# shield_biasa.net
KiCad netlist of a schematic drawn in EAGLE
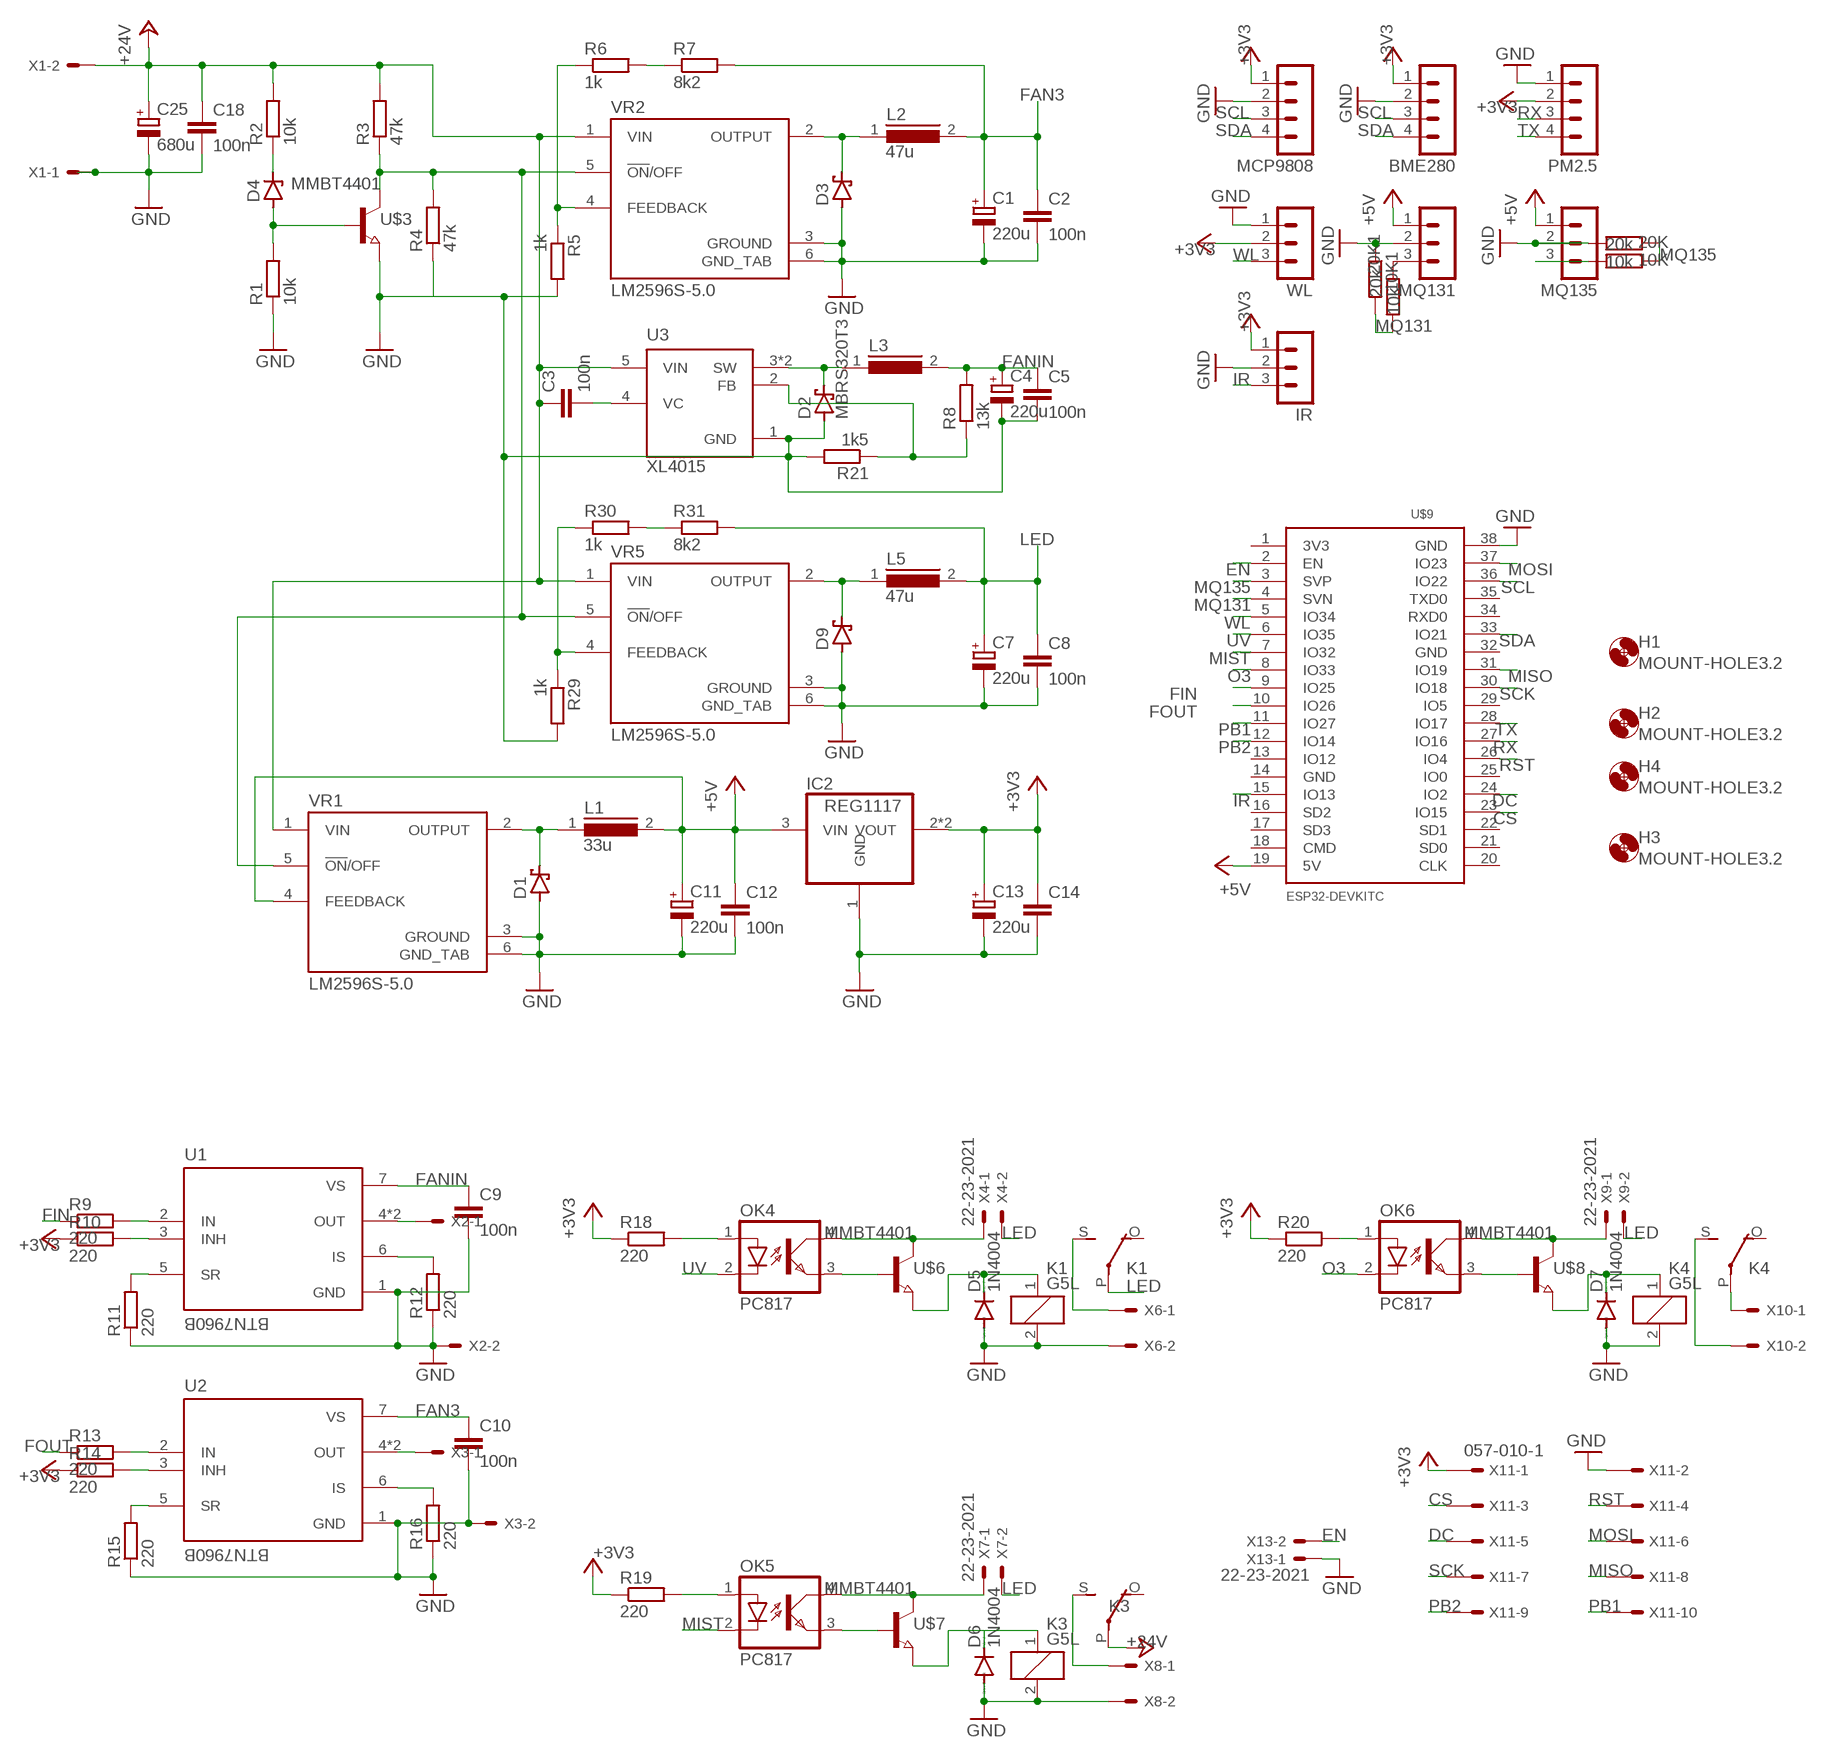
[diagram p0: schematic, sheet 1]

(export (version "E")
  (design (tool "Eeschema 10.0.6"))
  (components
    (comp (ref "10K")
      (value "10k")
      (footprint "eagle-import:R0805")
      (libsource (lib "eagle-import") (part "R-EU_R0805"))
    )
    (comp (ref "10K1")
      (value "10k")
      (footprint "eagle-import:R0805")
      (libsource (lib "eagle-import") (part "R-EU_R0805"))
    )
    (comp (ref "20K")
      (value "20k")
      (footprint "eagle-import:R0805")
      (libsource (lib "eagle-import") (part "R-EU_R0805"))
    )
    (comp (ref "20K1")
      (value "20k")
      (footprint "eagle-import:R0805")
      (libsource (lib "eagle-import") (part "R-EU_R0805"))
    )
    (comp (ref "BME280")
      (value "MA04-1")
      (footprint "eagle-import:MA04-1")
      (libsource (lib "eagle-import") (part "MA04-1"))
    )
    (comp (ref "C1")
      (value "220u")
      (footprint "eagle-import:153CLV-0605")
      (libsource (lib "eagle-import") (part "CPOL-EU153CLV-0605"))
    )
    (comp (ref "C2")
      (value "100n")
      (footprint "eagle-import:C0805")
      (libsource (lib "eagle-import") (part "C-EUC0805"))
    )
    (comp (ref "C3")
      (value "100n")
      (footprint "eagle-import:C0805")
      (libsource (lib "eagle-import") (part "C-EUC0805"))
    )
    (comp (ref "C4")
      (value "220u")
      (footprint "eagle-import:153CLV-0605")
      (libsource (lib "eagle-import") (part "CPOL-EU153CLV-0605"))
    )
    (comp (ref "C5")
      (value "100n")
      (footprint "eagle-import:C0805")
      (libsource (lib "eagle-import") (part "C-EUC0805"))
    )
    (comp (ref "C7")
      (value "220u")
      (footprint "eagle-import:153CLV-0605")
      (libsource (lib "eagle-import") (part "CPOL-EU153CLV-0605"))
    )
    (comp (ref "C8")
      (value "100n")
      (footprint "eagle-import:C0805")
      (libsource (lib "eagle-import") (part "C-EUC0805"))
    )
    (comp (ref "C9")
      (value "100n")
      (footprint "eagle-import:C0805")
      (libsource (lib "eagle-import") (part "C-EUC0805"))
    )
    (comp (ref "C10")
      (value "100n")
      (footprint "eagle-import:C0805")
      (libsource (lib "eagle-import") (part "C-EUC0805"))
    )
    (comp (ref "C11")
      (value "220u")
      (footprint "eagle-import:153CLV-0605")
      (libsource (lib "eagle-import") (part "CPOL-EU153CLV-0605"))
    )
    (comp (ref "C12")
      (value "100n")
      (footprint "eagle-import:C0805")
      (libsource (lib "eagle-import") (part "C-EUC0805"))
    )
    (comp (ref "C13")
      (value "220u")
      (footprint "eagle-import:153CLV-0605")
      (libsource (lib "eagle-import") (part "CPOL-EU153CLV-0605"))
    )
    (comp (ref "C14")
      (value "100n")
      (footprint "eagle-import:C0805")
      (libsource (lib "eagle-import") (part "C-EUC0805"))
    )
    (comp (ref "C18")
      (value "100n")
      (footprint "eagle-import:C0805")
      (libsource (lib "eagle-import") (part "C-EUC0805"))
    )
    (comp (ref "C25")
      (value "680u")
      (footprint "eagle-import:150CLZ-1010")
      (libsource (lib "eagle-import") (part "CPOL-EU150CLZ-1010"))
    )
    (comp (ref "D1")
      (value "SCHOTTKY-DIODESMD")
      (footprint "eagle-import:SMB")
      (libsource (lib "eagle-import") (part "SCHOTTKY-DIODESMD"))
    )
    (comp (ref "D2")
      (value "MBRS320T3")
      (footprint "eagle-import:SMC")
      (libsource (lib "eagle-import") (part "MBRS30T32"))
    )
    (comp (ref "D3")
      (value "SCHOTTKY-DIODESMD")
      (footprint "eagle-import:SMB")
      (libsource (lib "eagle-import") (part "SCHOTTKY-DIODESMD"))
    )
    (comp (ref "D4")
      (value "ZENER-DIODESOD80C")
      (footprint "eagle-import:SOD80C")
      (libsource (lib "eagle-import") (part "ZENER-DIODESOD80C"))
    )
    (comp (ref "D5")
      (value "1N4004")
      (footprint "eagle-import:DO41-10")
      (libsource (lib "eagle-import") (part "1N4004"))
    )
    (comp (ref "D6")
      (value "1N4004")
      (footprint "eagle-import:DO41-10")
      (libsource (lib "eagle-import") (part "1N4004"))
    )
    (comp (ref "D7")
      (value "1N4004")
      (footprint "eagle-import:DO41-10")
      (libsource (lib "eagle-import") (part "1N4004"))
    )
    (comp (ref "D9")
      (value "SCHOTTKY-DIODESMD")
      (footprint "eagle-import:SMB")
      (libsource (lib "eagle-import") (part "SCHOTTKY-DIODESMD"))
    )
    (comp (ref "H1")
      (value "MOUNT-HOLE3.2")
      (footprint "eagle-import:3,2")
      (libsource (lib "eagle-import") (part "MOUNT-HOLE3.2"))
    )
    (comp (ref "H2")
      (value "MOUNT-HOLE3.2")
      (footprint "eagle-import:3,2")
      (libsource (lib "eagle-import") (part "MOUNT-HOLE3.2"))
    )
    (comp (ref "H3")
      (value "MOUNT-HOLE3.2")
      (footprint "eagle-import:3,2")
      (libsource (lib "eagle-import") (part "MOUNT-HOLE3.2"))
    )
    (comp (ref "H4")
      (value "MOUNT-HOLE3.2")
      (footprint "eagle-import:3,2")
      (libsource (lib "eagle-import") (part "MOUNT-HOLE3.2"))
    )
    (comp (ref "IC2")
      (value "REG1117")
      (footprint "eagle-import:SOT223")
      (libsource (lib "eagle-import") (part "REG1117"))
    )
    (comp (ref "IR")
      (value "MA03-1")
      (footprint "eagle-import:MA03-1")
      (libsource (lib "eagle-import") (part "MA03-1"))
    )
    (comp (ref "K1")
      (value "G5L")
      (footprint "eagle-import:G5LE")
      (libsource (lib "eagle-import") (part "G5L"))
    )
    (comp (ref "K3")
      (value "G5L")
      (footprint "eagle-import:G5LE")
      (libsource (lib "eagle-import") (part "G5L"))
    )
    (comp (ref "K4")
      (value "G5L")
      (footprint "eagle-import:G5LE")
      (libsource (lib "eagle-import") (part "G5L"))
    )
    (comp (ref "L1")
      (value "33u")
      (footprint "eagle-import:DR125")
      (libsource (lib "eagle-import") (part "DR125"))
    )
    (comp (ref "L2")
      (value "47u")
      (footprint "eagle-import:DR125")
      (libsource (lib "eagle-import") (part "DR125"))
    )
    (comp (ref "L3")
      (value "R1003DS11")
      (footprint "eagle-import:S11-10")
      (libsource (lib "eagle-import") (part "R1003DS11"))
    )
    (comp (ref "L5")
      (value "47u")
      (footprint "eagle-import:DR125")
      (libsource (lib "eagle-import") (part "DR125"))
    )
    (comp (ref "MCP9808")
      (value "MA04-1")
      (footprint "eagle-import:MA04-1")
      (libsource (lib "eagle-import") (part "MA04-1"))
    )
    (comp (ref "MQ131")
      (value "MA03-1")
      (footprint "eagle-import:MA03-1")
      (libsource (lib "eagle-import") (part "MA03-1"))
    )
    (comp (ref "MQ135")
      (value "MA03-1")
      (footprint "eagle-import:MA03-1")
      (libsource (lib "eagle-import") (part "MA03-1"))
    )
    (comp (ref "OK4")
      (value "PC817")
      (footprint "eagle-import:DIL04")
      (fields (field (name "MPN") "PC817X4J000F"))
      (libsource (lib "eagle-import") (part "PC817"))
    )
    (comp (ref "OK5")
      (value "PC817")
      (footprint "eagle-import:DIL04")
      (fields (field (name "MPN") "PC817X4J000F"))
      (libsource (lib "eagle-import") (part "PC817"))
    )
    (comp (ref "OK6")
      (value "PC817")
      (footprint "eagle-import:DIL04")
      (fields (field (name "MPN") "PC817X4J000F"))
      (libsource (lib "eagle-import") (part "PC817"))
    )
    (comp (ref "PM2.5")
      (value "MA04-1")
      (footprint "eagle-import:MA04-1")
      (libsource (lib "eagle-import") (part "MA04-1"))
    )
    (comp (ref "R1")
      (value "10k")
      (footprint "eagle-import:R0805")
      (libsource (lib "eagle-import") (part "R-EU_R0805"))
    )
    (comp (ref "R2")
      (value "10k")
      (footprint "eagle-import:R0805")
      (libsource (lib "eagle-import") (part "R-EU_R0805"))
    )
    (comp (ref "R3")
      (value "47k")
      (footprint "eagle-import:R0805")
      (libsource (lib "eagle-import") (part "R-EU_R0805"))
    )
    (comp (ref "R4")
      (value "47k")
      (footprint "eagle-import:R0805")
      (libsource (lib "eagle-import") (part "R-EU_R0805"))
    )
    (comp (ref "R5")
      (value "1k")
      (footprint "eagle-import:R0805")
      (libsource (lib "eagle-import") (part "R-EU_R0805"))
    )
    (comp (ref "R6")
      (value "1k")
      (footprint "eagle-import:R0805")
      (libsource (lib "eagle-import") (part "R-EU_R0805"))
    )
    (comp (ref "R7")
      (value "8k2")
      (footprint "eagle-import:R0805")
      (libsource (lib "eagle-import") (part "R-EU_R0805"))
    )
    (comp (ref "R8")
      (value "13k")
      (footprint "eagle-import:R0805")
      (libsource (lib "eagle-import") (part "R-EU_R0805"))
    )
    (comp (ref "R9")
      (value "220")
      (footprint "eagle-import:R0805")
      (libsource (lib "eagle-import") (part "R-EU_R0805"))
    )
    (comp (ref "R10")
      (value "220")
      (footprint "eagle-import:R0805")
      (libsource (lib "eagle-import") (part "R-EU_R0805"))
    )
    (comp (ref "R11")
      (value "220")
      (footprint "eagle-import:R0805")
      (libsource (lib "eagle-import") (part "R-EU_R0805"))
    )
    (comp (ref "R12")
      (value "220")
      (footprint "eagle-import:R0805")
      (libsource (lib "eagle-import") (part "R-EU_R0805"))
    )
    (comp (ref "R13")
      (value "220")
      (footprint "eagle-import:R0805")
      (libsource (lib "eagle-import") (part "R-EU_R0805"))
    )
    (comp (ref "R14")
      (value "220")
      (footprint "eagle-import:R0805")
      (libsource (lib "eagle-import") (part "R-EU_R0805"))
    )
    (comp (ref "R15")
      (value "220")
      (footprint "eagle-import:R0805")
      (libsource (lib "eagle-import") (part "R-EU_R0805"))
    )
    (comp (ref "R16")
      (value "220")
      (footprint "eagle-import:R0805")
      (libsource (lib "eagle-import") (part "R-EU_R0805"))
    )
    (comp (ref "R18")
      (value "220")
      (footprint "eagle-import:R0805")
      (libsource (lib "eagle-import") (part "R-EU_R0805"))
    )
    (comp (ref "R19")
      (value "220")
      (footprint "eagle-import:R0805")
      (libsource (lib "eagle-import") (part "R-EU_R0805"))
    )
    (comp (ref "R20")
      (value "220")
      (footprint "eagle-import:R0805")
      (libsource (lib "eagle-import") (part "R-EU_R0805"))
    )
    (comp (ref "R21")
      (value "1k5")
      (footprint "eagle-import:R0805")
      (libsource (lib "eagle-import") (part "R-EU_R0805"))
    )
    (comp (ref "R29")
      (value "1k")
      (footprint "eagle-import:R0805")
      (libsource (lib "eagle-import") (part "R-EU_R0805"))
    )
    (comp (ref "R30")
      (value "1k")
      (footprint "eagle-import:R0805")
      (libsource (lib "eagle-import") (part "R-EU_R0805"))
    )
    (comp (ref "R31")
      (value "8k2")
      (footprint "eagle-import:R0805")
      (libsource (lib "eagle-import") (part "R-EU_R0805"))
    )
    (comp (ref "U$3")
      (value "MMBT4401")
      (footprint "eagle-import:SOT23-RAEDEN")
      (fields (field (name "MF") "ON Semiconductor"))
      (libsource (lib "eagle-import") (part "MMBT4401"))
    )
    (comp (ref "U$6")
      (value "MMBT4401")
      (footprint "eagle-import:SOT23-RAEDEN")
      (fields (field (name "MF") "ON Semiconductor"))
      (libsource (lib "eagle-import") (part "MMBT4401"))
    )
    (comp (ref "U$7")
      (value "MMBT4401")
      (footprint "eagle-import:SOT23-RAEDEN")
      (fields (field (name "MF") "ON Semiconductor"))
      (libsource (lib "eagle-import") (part "MMBT4401"))
    )
    (comp (ref "U$8")
      (value "MMBT4401")
      (footprint "eagle-import:SOT23-RAEDEN")
      (fields (field (name "MF") "ON Semiconductor"))
      (libsource (lib "eagle-import") (part "MMBT4401"))
    )
    (comp (ref "U$9")
      (value "ESP32DEVKITC")
      (footprint "eagle-import:ESP32-DEVKITC")
      (libsource (lib "eagle-import") (part "ESP32DEVKITC"))
    )
    (comp (ref "U1")
      (value "BTN7960B")
      (footprint "eagle-import:IC_BTN7960B")
      (fields (field (name "MF") "Infineon Technologies"))
      (libsource (lib "eagle-import") (part "BTN7960B"))
    )
    (comp (ref "U2")
      (value "BTN7960B")
      (footprint "eagle-import:IC_BTN7960B")
      (fields (field (name "MF") "Infineon Technologies"))
      (libsource (lib "eagle-import") (part "BTN7960B"))
    )
    (comp (ref "U3")
      (value "XL4015")
      (footprint "eagle-import:CONV_XL4015")
      (fields (field (name "MF") "XLSEMI"))
      (libsource (lib "eagle-import") (part "XL4015"))
    )
    (comp (ref "VR1")
      (value "LM2596S-5.0")
      (footprint "eagle-import:TO170P1524X483-6N")
      (fields (field (name "MF") "Texas Instruments") (field (name "MP") "LM2596S-5.0/NOPB"))
      (libsource (lib "eagle-import") (part "LM2596S-5.0"))
    )
    (comp (ref "VR2")
      (value "LM2596S-5.0")
      (footprint "eagle-import:TO170P1524X483-6N")
      (fields (field (name "MF") "Texas Instruments") (field (name "MP") "LM2596S-5.0/NOPB"))
      (libsource (lib "eagle-import") (part "LM2596S-5.0"))
    )
    (comp (ref "VR5")
      (value "LM2596S-5.0")
      (footprint "eagle-import:TO170P1524X483-6N")
      (fields (field (name "MF") "Texas Instruments") (field (name "MP") "LM2596S-5.0/NOPB"))
      (libsource (lib "eagle-import") (part "LM2596S-5.0"))
    )
    (comp (ref "WL")
      (value "MA03-1")
      (footprint "eagle-import:MA03-1")
      (libsource (lib "eagle-import") (part "MA03-1"))
    )
    (comp (ref "X1")
      (value "KK-156-2")
      (footprint "eagle-import:KK-156-2")
      (fields (field (name "MF") "MOLEX"))
      (libsource (lib "eagle-import") (part "KK-156-2"))
    )
    (comp (ref "X2")
      (value "KK-156-2")
      (footprint "eagle-import:KK-156-2")
      (fields (field (name "MF") "MOLEX"))
      (libsource (lib "eagle-import") (part "KK-156-2"))
    )
    (comp (ref "X3")
      (value "KK-156-2")
      (footprint "eagle-import:KK-156-2")
      (fields (field (name "MF") "MOLEX"))
      (libsource (lib "eagle-import") (part "KK-156-2"))
    )
    (comp (ref "X4")
      (value "22-23-2021")
      (footprint "eagle-import:22-23-2021")
      (fields (field (name "MF") "MOLEX"))
      (libsource (lib "eagle-import") (part "22-23-2021"))
    )
    (comp (ref "X6")
      (value "KK-156-2")
      (footprint "eagle-import:KK-156-2")
      (fields (field (name "MF") "MOLEX"))
      (libsource (lib "eagle-import") (part "KK-156-2"))
    )
    (comp (ref "X7")
      (value "22-23-2021")
      (footprint "eagle-import:22-23-2021")
      (fields (field (name "MF") "MOLEX"))
      (libsource (lib "eagle-import") (part "22-23-2021"))
    )
    (comp (ref "X8")
      (value "KK-156-2")
      (footprint "eagle-import:KK-156-2")
      (fields (field (name "MF") "MOLEX"))
      (libsource (lib "eagle-import") (part "KK-156-2"))
    )
    (comp (ref "X9")
      (value "22-23-2021")
      (footprint "eagle-import:22-23-2021")
      (fields (field (name "MF") "MOLEX"))
      (libsource (lib "eagle-import") (part "22-23-2021"))
    )
    (comp (ref "X10")
      (value "KK-156-2")
      (footprint "eagle-import:KK-156-2")
      (fields (field (name "MF") "MOLEX"))
      (libsource (lib "eagle-import") (part "KK-156-2"))
    )
    (comp (ref "X11")
      (value "057-010-1")
      (footprint "eagle-import:057-010-1")
      (libsource (lib "eagle-import") (part "057-010-1"))
    )
    (comp (ref "X13")
      (value "22-23-2021")
      (footprint "eagle-import:22-23-2021")
      (fields (field (name "MF") "MOLEX"))
      (libsource (lib "eagle-import") (part "22-23-2021"))
    )
  )
  (nets
    (net (code "1") (name "+3V3") (class "Default")
      (node (ref "BME280") (pin "1") (pinfunction "1_1") (pintype "passive"))
      (node (ref "C13") (pin "+") (pinfunction "+_+") (pintype "passive"))
      (node (ref "C14") (pin "1") (pinfunction "1_1") (pintype "passive"))
      (node (ref "IC2") (pin "2") (pinfunction "VOUT_2") (pintype "output"))
      (node (ref "IC2") (pin "4") (pinfunction "VOUT_4") (pintype "output"))
      (node (ref "IR") (pin "1") (pinfunction "1_1") (pintype "passive"))
      (node (ref "MCP9808") (pin "1") (pinfunction "1_1") (pintype "passive"))
      (node (ref "PM2.5") (pin "2") (pinfunction "2_2") (pintype "passive"))
      (node (ref "R10") (pin "1") (pinfunction "1_1") (pintype "passive"))
      (node (ref "R14") (pin "1") (pinfunction "1_1") (pintype "passive"))
      (node (ref "R18") (pin "1") (pinfunction "1_1") (pintype "passive"))
      (node (ref "R19") (pin "1") (pinfunction "1_1") (pintype "passive"))
      (node (ref "R20") (pin "1") (pinfunction "1_1") (pintype "passive"))
      (node (ref "WL") (pin "2") (pinfunction "2_2") (pintype "passive"))
      (node (ref "X11") (pin "1") (pinfunction "S_1") (pintype "passive"))
    )
    (net (code "2") (name "+5V") (class "Default")
      (node (ref "C11") (pin "+") (pinfunction "+_+") (pintype "passive"))
      (node (ref "C12") (pin "1") (pinfunction "1_1") (pintype "passive"))
      (node (ref "IC2") (pin "3") (pinfunction "VIN_3") (pintype "input"))
      (node (ref "L1") (pin "2") (pinfunction "2_2") (pintype "passive"))
      (node (ref "MQ131") (pin "1") (pinfunction "1_1") (pintype "passive"))
      (node (ref "MQ135") (pin "1") (pinfunction "1_1") (pintype "passive"))
      (node (ref "U$9") (pin "19") (pinfunction "5V_19") (pintype "bidirectional"))
      (node (ref "VR1") (pin "4") (pinfunction "FEEDBACK_4") (pintype "input"))
    )
    (net (code "3") (name "+24V") (class "Default")
      (node (ref "C18") (pin "1") (pinfunction "1_1") (pintype "passive"))
      (node (ref "C25") (pin "+") (pinfunction "+_+") (pintype "passive"))
      (node (ref "C3") (pin "1") (pinfunction "1_1") (pintype "passive"))
      (node (ref "K3") (pin "P") (pinfunction "P_P") (pintype "passive"))
      (node (ref "R2") (pin "2") (pinfunction "2_2") (pintype "passive"))
      (node (ref "R3") (pin "2") (pinfunction "2_2") (pintype "passive"))
      (node (ref "U3") (pin "5") (pinfunction "VIN_5") (pintype "input"))
      (node (ref "VR1") (pin "1") (pinfunction "VIN_1") (pintype "input"))
      (node (ref "VR2") (pin "1") (pinfunction "VIN_1") (pintype "input"))
      (node (ref "VR5") (pin "1") (pinfunction "VIN_1") (pintype "input"))
      (node (ref "X1") (pin "2") (pinfunction "S_2") (pintype "passive"))
    )
    (net (code "4") (name "/CS") (class "Default")
      (node (ref "U$9") (pin "23") (pinfunction "IO15_23") (pintype "bidirectional"))
      (node (ref "X11") (pin "3") (pinfunction "S_3") (pintype "passive"))
    )
    (net (code "5") (name "/DC") (class "Default")
      (node (ref "U$9") (pin "24") (pinfunction "IO2_24") (pintype "bidirectional"))
      (node (ref "X11") (pin "5") (pinfunction "S_5") (pintype "passive"))
    )
    (net (code "6") (name "/EN") (class "Default")
      (node (ref "U$9") (pin "2") (pinfunction "EN_2") (pintype "bidirectional"))
      (node (ref "X13") (pin "2") (pinfunction "S_2") (pintype "passive"))
    )
    (net (code "7") (name "/FAN3") (class "Default")
      (node (ref "C1") (pin "+") (pinfunction "+_+") (pintype "passive"))
      (node (ref "C10") (pin "1") (pinfunction "1_1") (pintype "passive"))
      (node (ref "C2") (pin "1") (pinfunction "1_1") (pintype "passive"))
      (node (ref "L2") (pin "2") (pinfunction "2_2") (pintype "passive"))
      (node (ref "R7") (pin "2") (pinfunction "2_2") (pintype "passive"))
      (node (ref "U2") (pin "7") (pinfunction "VS_7") (pintype "power_in"))
    )
    (net (code "8") (name "/FANIN") (class "Default")
      (node (ref "C4") (pin "+") (pinfunction "+_+") (pintype "passive"))
      (node (ref "C5") (pin "1") (pinfunction "1_1") (pintype "passive"))
      (node (ref "C9") (pin "1") (pinfunction "1_1") (pintype "passive"))
      (node (ref "L3") (pin "2") (pinfunction "2_2") (pintype "passive"))
      (node (ref "R8") (pin "2") (pinfunction "2_2") (pintype "passive"))
      (node (ref "U1") (pin "7") (pinfunction "VS_7") (pintype "power_in"))
    )
    (net (code "9") (name "/FIN") (class "Default")
      (node (ref "R9") (pin "1") (pinfunction "1_1") (pintype "passive"))
      (node (ref "U$9") (pin "9") (pinfunction "IO25_9") (pintype "bidirectional"))
    )
    (net (code "10") (name "/FOUT") (class "Default")
      (node (ref "R13") (pin "1") (pinfunction "1_1") (pintype "passive"))
      (node (ref "U$9") (pin "10") (pinfunction "IO26_10") (pintype "bidirectional"))
    )
    (net (code "11") (name "/IR") (class "Default")
      (node (ref "IR") (pin "3") (pinfunction "3_3") (pintype "passive"))
      (node (ref "U$9") (pin "15") (pinfunction "IO13_15") (pintype "bidirectional"))
    )
    (net (code "12") (name "/LED") (class "Default")
      (node (ref "C7") (pin "+") (pinfunction "+_+") (pintype "passive"))
      (node (ref "C8") (pin "1") (pinfunction "1_1") (pintype "passive"))
      (node (ref "K1") (pin "P") (pinfunction "P_P") (pintype "passive"))
      (node (ref "L5") (pin "2") (pinfunction "2_2") (pintype "passive"))
      (node (ref "R31") (pin "2") (pinfunction "2_2") (pintype "passive"))
      (node (ref "X4") (pin "2") (pinfunction "S_2") (pintype "passive"))
      (node (ref "X7") (pin "2") (pinfunction "S_2") (pintype "passive"))
      (node (ref "X9") (pin "2") (pinfunction "S_2") (pintype "passive"))
    )
    (net (code "13") (name "/MISO") (class "Default")
      (node (ref "U$9") (pin "31") (pinfunction "IO19_31") (pintype "bidirectional"))
      (node (ref "X11") (pin "8") (pinfunction "S_8") (pintype "passive"))
    )
    (net (code "14") (name "/MIST") (class "Default")
      (node (ref "OK5") (pin "2") (pinfunction "C_2") (pintype "passive"))
      (node (ref "U$9") (pin "7") (pinfunction "IO32_7") (pintype "bidirectional"))
    )
    (net (code "15") (name "/MOSI") (class "Default")
      (node (ref "U$9") (pin "37") (pinfunction "IO23_37") (pintype "bidirectional"))
      (node (ref "X11") (pin "6") (pinfunction "S_6") (pintype "passive"))
    )
    (net (code "16") (name "/MQ131") (class "Default")
      (node (ref "10K1") (pin "2") (pinfunction "2_2") (pintype "passive"))
      (node (ref "20K1") (pin "2") (pinfunction "2_2") (pintype "passive"))
      (node (ref "U$9") (pin "4") (pinfunction "SVN_4") (pintype "bidirectional"))
    )
    (net (code "17") (name "/MQ135") (class "Default")
      (node (ref "10K") (pin "1") (pinfunction "1_1") (pintype "passive"))
      (node (ref "20K") (pin "1") (pinfunction "1_1") (pintype "passive"))
      (node (ref "U$9") (pin "3") (pinfunction "SVP_3") (pintype "bidirectional"))
    )
    (net (code "18") (name "/O3") (class "Default")
      (node (ref "OK6") (pin "2") (pinfunction "C_2") (pintype "passive"))
      (node (ref "U$9") (pin "8") (pinfunction "IO33_8") (pintype "bidirectional"))
    )
    (net (code "19") (name "/PB1") (class "Default")
      (node (ref "U$9") (pin "11") (pinfunction "IO27_11") (pintype "bidirectional"))
      (node (ref "X11") (pin "10") (pinfunction "S_10") (pintype "passive"))
    )
    (net (code "20") (name "/PB2") (class "Default")
      (node (ref "U$9") (pin "12") (pinfunction "IO14_12") (pintype "bidirectional"))
      (node (ref "X11") (pin "9") (pinfunction "S_9") (pintype "passive"))
    )
    (net (code "21") (name "/RST") (class "Default")
      (node (ref "U$9") (pin "26") (pinfunction "IO4_26") (pintype "bidirectional"))
      (node (ref "X11") (pin "4") (pinfunction "S_4") (pintype "passive"))
    )
    (net (code "22") (name "/RX") (class "Default")
      (node (ref "PM2.5") (pin "3") (pinfunction "3_3") (pintype "passive"))
      (node (ref "U$9") (pin "27") (pinfunction "IO16_27") (pintype "bidirectional"))
    )
    (net (code "23") (name "/SCK") (class "Default")
      (node (ref "U$9") (pin "30") (pinfunction "IO18_30") (pintype "bidirectional"))
      (node (ref "X11") (pin "7") (pinfunction "S_7") (pintype "passive"))
    )
    (net (code "24") (name "/SCL") (class "Default")
      (node (ref "BME280") (pin "3") (pinfunction "3_3") (pintype "passive"))
      (node (ref "MCP9808") (pin "3") (pinfunction "3_3") (pintype "passive"))
      (node (ref "U$9") (pin "36") (pinfunction "IO22_36") (pintype "bidirectional"))
    )
    (net (code "25") (name "/SDA") (class "Default")
      (node (ref "BME280") (pin "4") (pinfunction "4_4") (pintype "passive"))
      (node (ref "MCP9808") (pin "4") (pinfunction "4_4") (pintype "passive"))
      (node (ref "U$9") (pin "33") (pinfunction "IO21_33") (pintype "bidirectional"))
    )
    (net (code "26") (name "/TX") (class "Default")
      (node (ref "PM2.5") (pin "4") (pinfunction "4_4") (pintype "passive"))
      (node (ref "U$9") (pin "28") (pinfunction "IO17_28") (pintype "bidirectional"))
    )
    (net (code "27") (name "/UV") (class "Default")
      (node (ref "OK4") (pin "2") (pinfunction "C_2") (pintype "passive"))
      (node (ref "U$9") (pin "6") (pinfunction "IO35_6") (pintype "bidirectional"))
    )
    (net (code "28") (name "/WL") (class "Default")
      (node (ref "U$9") (pin "5") (pinfunction "IO34_5") (pintype "bidirectional"))
      (node (ref "WL") (pin "3") (pinfunction "3_3") (pintype "passive"))
    )
    (net (code "29") (name "GND") (class "Default")
      (node (ref "20K") (pin "2") (pinfunction "2_2") (pintype "passive"))
      (node (ref "20K1") (pin "1") (pinfunction "1_1") (pintype "passive"))
      (node (ref "BME280") (pin "2") (pinfunction "2_2") (pintype "passive"))
      (node (ref "C1") (pin "-") (pinfunction "-_-") (pintype "passive"))
      (node (ref "C10") (pin "2") (pinfunction "2_2") (pintype "passive"))
      (node (ref "C11") (pin "-") (pinfunction "-_-") (pintype "passive"))
      (node (ref "C12") (pin "2") (pinfunction "2_2") (pintype "passive"))
      (node (ref "C13") (pin "-") (pinfunction "-_-") (pintype "passive"))
      (node (ref "C14") (pin "2") (pinfunction "2_2") (pintype "passive"))
      (node (ref "C18") (pin "2") (pinfunction "2_2") (pintype "passive"))
      (node (ref "C2") (pin "2") (pinfunction "2_2") (pintype "passive"))
      (node (ref "C25") (pin "-") (pinfunction "-_-") (pintype "passive"))
      (node (ref "C4") (pin "-") (pinfunction "-_-") (pintype "passive"))
      (node (ref "C5") (pin "2") (pinfunction "2_2") (pintype "passive"))
      (node (ref "C7") (pin "-") (pinfunction "-_-") (pintype "passive"))
      (node (ref "C8") (pin "2") (pinfunction "2_2") (pintype "passive"))
      (node (ref "C9") (pin "2") (pinfunction "2_2") (pintype "passive"))
      (node (ref "D1") (pin "A") (pinfunction "A_A") (pintype "passive"))
      (node (ref "D2") (pin "A") (pinfunction "A_A") (pintype "passive"))
      (node (ref "D3") (pin "A") (pinfunction "A_A") (pintype "passive"))
      (node (ref "D5") (pin "A") (pinfunction "A_A") (pintype "passive"))
      (node (ref "D6") (pin "A") (pinfunction "A_A") (pintype "passive"))
      (node (ref "D7") (pin "A") (pinfunction "A_A") (pintype "passive"))
      (node (ref "D9") (pin "A") (pinfunction "A_A") (pintype "passive"))
      (node (ref "IC2") (pin "1") (pinfunction "GND_1") (pintype "power_in"))
      (node (ref "IR") (pin "2") (pinfunction "2_2") (pintype "passive"))
      (node (ref "K1") (pin "2") (pinfunction "2_2") (pintype "passive"))
      (node (ref "K3") (pin "2") (pinfunction "2_2") (pintype "passive"))
      (node (ref "K4") (pin "2") (pinfunction "2_2") (pintype "passive"))
      (node (ref "MCP9808") (pin "2") (pinfunction "2_2") (pintype "passive"))
      (node (ref "MQ131") (pin "2") (pinfunction "2_2") (pintype "passive"))
      (node (ref "MQ135") (pin "2") (pinfunction "2_2") (pintype "passive"))
      (node (ref "PM2.5") (pin "1") (pinfunction "1_1") (pintype "passive"))
      (node (ref "R1") (pin "1") (pinfunction "1_1") (pintype "passive"))
      (node (ref "R11") (pin "1") (pinfunction "1_1") (pintype "passive"))
      (node (ref "R12") (pin "1") (pinfunction "1_1") (pintype "passive"))
      (node (ref "R15") (pin "1") (pinfunction "1_1") (pintype "passive"))
      (node (ref "R16") (pin "1") (pinfunction "1_1") (pintype "passive"))
      (node (ref "R21") (pin "2") (pinfunction "2_2") (pintype "passive"))
      (node (ref "R29") (pin "2") (pinfunction "2_2") (pintype "passive"))
      (node (ref "R4") (pin "1") (pinfunction "1_1") (pintype "passive"))
      (node (ref "R5") (pin "2") (pinfunction "2_2") (pintype "passive"))
      (node (ref "U$3") (pin "E") (pinfunction "E_E") (pintype "passive"))
      (node (ref "U$9") (pin "38") (pinfunction "GND_38") (pintype "bidirectional"))
      (node (ref "U1") (pin "1") (pinfunction "GND_1") (pintype "power_in"))
      (node (ref "U2") (pin "1") (pinfunction "GND_1") (pintype "power_in"))
      (node (ref "U3") (pin "1") (pinfunction "GND_1") (pintype "power_in"))
      (node (ref "VR1") (pin "3") (pinfunction "GROUND_3") (pintype "power_in"))
      (node (ref "VR1") (pin "6") (pinfunction "GND_TAB_6") (pintype "power_in"))
      (node (ref "VR2") (pin "3") (pinfunction "GROUND_3") (pintype "power_in"))
      (node (ref "VR2") (pin "6") (pinfunction "GND_TAB_6") (pintype "power_in"))
      (node (ref "VR5") (pin "3") (pinfunction "GROUND_3") (pintype "power_in"))
      (node (ref "VR5") (pin "6") (pinfunction "GND_TAB_6") (pintype "power_in"))
      (node (ref "WL") (pin "1") (pinfunction "1_1") (pintype "passive"))
      (node (ref "X1") (pin "1") (pinfunction "S_1") (pintype "passive"))
      (node (ref "X11") (pin "2") (pinfunction "S_2") (pintype "passive"))
      (node (ref "X13") (pin "1") (pinfunction "S_1") (pintype "passive"))
      (node (ref "X2") (pin "2") (pinfunction "S_2") (pintype "passive"))
      (node (ref "X3") (pin "2") (pinfunction "S_2") (pintype "passive"))
      (node (ref "X6") (pin "2") (pinfunction "S_2") (pintype "passive"))
      (node (ref "X8") (pin "2") (pinfunction "S_2") (pintype "passive"))
    )
    (net (code "30") (name "Net-(10K-Pad2)") (class "Default")
      (node (ref "10K") (pin "2") (pinfunction "2_2") (pintype "passive"))
      (node (ref "MQ135") (pin "3") (pinfunction "3_3") (pintype "passive"))
    )
    (net (code "31") (name "Net-(10K1-Pad1)") (class "Default")
      (node (ref "10K1") (pin "1") (pinfunction "1_1") (pintype "passive"))
      (node (ref "MQ131") (pin "3") (pinfunction "3_3") (pintype "passive"))
    )
    (net (code "32") (name "Net-(D2-PadC)") (class "Default")
      (node (ref "D2") (pin "C") (pinfunction "C_C") (pintype "passive"))
      (node (ref "L3") (pin "1") (pinfunction "1_1") (pintype "passive"))
      (node (ref "U3") (pin "3") (pinfunction "SW_3") (pintype "output"))
      (node (ref "U3") (pin "3.1") (pinfunction "SW_3.1") (pintype "output"))
    )
    (net (code "33") (name "Net-(D4-PadA)") (class "Default")
      (node (ref "D4") (pin "A") (pinfunction "A_A") (pintype "passive"))
      (node (ref "R1") (pin "2") (pinfunction "2_2") (pintype "passive"))
      (node (ref "U$3") (pin "B") (pinfunction "B_B") (pintype "passive"))
    )
    (net (code "34") (name "Net-(D4-PadC)") (class "Default")
      (node (ref "D4") (pin "C") (pinfunction "C_C") (pintype "passive"))
      (node (ref "R2") (pin "1") (pinfunction "1_1") (pintype "passive"))
    )
    (net (code "35") (name "Net-(D5-PadC)") (class "Default")
      (node (ref "D5") (pin "C") (pinfunction "C_C") (pintype "passive"))
      (node (ref "K1") (pin "1") (pinfunction "1_1") (pintype "passive"))
      (node (ref "U$6") (pin "E") (pinfunction "E_E") (pintype "passive"))
    )
    (net (code "36") (name "Net-(D6-PadC)") (class "Default")
      (node (ref "D6") (pin "C") (pinfunction "C_C") (pintype "passive"))
      (node (ref "K3") (pin "1") (pinfunction "1_1") (pintype "passive"))
      (node (ref "U$7") (pin "E") (pinfunction "E_E") (pintype "passive"))
    )
    (net (code "37") (name "Net-(D7-PadC)") (class "Default")
      (node (ref "D7") (pin "C") (pinfunction "C_C") (pintype "passive"))
      (node (ref "K4") (pin "1") (pinfunction "1_1") (pintype "passive"))
      (node (ref "U$8") (pin "E") (pinfunction "E_E") (pintype "passive"))
    )
    (net (code "38") (name "Net-(OK4-A)") (class "Default")
      (node (ref "OK4") (pin "1") (pinfunction "A_1") (pintype "passive"))
      (node (ref "R18") (pin "2") (pinfunction "2_2") (pintype "passive"))
    )
    (net (code "39") (name "Net-(OK4-COL)") (class "Default")
      (node (ref "OK4") (pin "4") (pinfunction "COL_4") (pintype "passive"))
      (node (ref "U$6") (pin "C") (pinfunction "C_C") (pintype "passive"))
      (node (ref "X4") (pin "1") (pinfunction "S_1") (pintype "passive"))
    )
    (net (code "40") (name "Net-(OK4-EMIT)") (class "Default")
      (node (ref "OK4") (pin "3") (pinfunction "EMIT_3") (pintype "passive"))
      (node (ref "U$6") (pin "B") (pinfunction "B_B") (pintype "passive"))
    )
    (net (code "41") (name "Net-(OK5-A)") (class "Default")
      (node (ref "OK5") (pin "1") (pinfunction "A_1") (pintype "passive"))
      (node (ref "R19") (pin "2") (pinfunction "2_2") (pintype "passive"))
    )
    (net (code "42") (name "Net-(OK5-COL)") (class "Default")
      (node (ref "OK5") (pin "4") (pinfunction "COL_4") (pintype "passive"))
      (node (ref "U$7") (pin "C") (pinfunction "C_C") (pintype "passive"))
      (node (ref "X7") (pin "1") (pinfunction "S_1") (pintype "passive"))
    )
    (net (code "43") (name "Net-(OK5-EMIT)") (class "Default")
      (node (ref "OK5") (pin "3") (pinfunction "EMIT_3") (pintype "passive"))
      (node (ref "U$7") (pin "B") (pinfunction "B_B") (pintype "passive"))
    )
    (net (code "44") (name "Net-(OK6-A)") (class "Default")
      (node (ref "OK6") (pin "1") (pinfunction "A_1") (pintype "passive"))
      (node (ref "R20") (pin "2") (pinfunction "2_2") (pintype "passive"))
    )
    (net (code "45") (name "Net-(OK6-COL)") (class "Default")
      (node (ref "OK6") (pin "4") (pinfunction "COL_4") (pintype "passive"))
      (node (ref "U$8") (pin "C") (pinfunction "C_C") (pintype "passive"))
      (node (ref "X9") (pin "1") (pinfunction "S_1") (pintype "passive"))
    )
    (net (code "46") (name "Net-(OK6-EMIT)") (class "Default")
      (node (ref "OK6") (pin "3") (pinfunction "EMIT_3") (pintype "passive"))
      (node (ref "U$8") (pin "B") (pinfunction "B_B") (pintype "passive"))
    )
    (net (code "47") (name "Net-(R6-Pad2)") (class "Default")
      (node (ref "R6") (pin "2") (pinfunction "2_2") (pintype "passive"))
      (node (ref "R7") (pin "1") (pinfunction "1_1") (pintype "passive"))
    )
    (net (code "48") (name "Net-(R30-Pad2)") (class "Default")
      (node (ref "R30") (pin "2") (pinfunction "2_2") (pintype "passive"))
      (node (ref "R31") (pin "1") (pinfunction "1_1") (pintype "passive"))
    )
    (net (code "49") (name "Net-(U1-IN)") (class "Default")
      (node (ref "R9") (pin "2") (pinfunction "2_2") (pintype "passive"))
      (node (ref "U1") (pin "2") (pinfunction "IN_2") (pintype "input"))
    )
    (net (code "50") (name "Net-(U1-INH)") (class "Default")
      (node (ref "R10") (pin "2") (pinfunction "2_2") (pintype "passive"))
      (node (ref "U1") (pin "3") (pinfunction "INH_3") (pintype "input"))
    )
    (net (code "51") (name "Net-(U1-IS)") (class "Default")
      (node (ref "R12") (pin "2") (pinfunction "2_2") (pintype "passive"))
      (node (ref "U1") (pin "6") (pinfunction "IS_6") (pintype "output"))
    )
    (net (code "52") (name "Net-(U1-SR)") (class "Default")
      (node (ref "R11") (pin "2") (pinfunction "2_2") (pintype "passive"))
      (node (ref "U1") (pin "5") (pinfunction "SR_5") (pintype "input"))
    )
    (net (code "53") (name "Net-(U2-IN)") (class "Default")
      (node (ref "R13") (pin "2") (pinfunction "2_2") (pintype "passive"))
      (node (ref "U2") (pin "2") (pinfunction "IN_2") (pintype "input"))
    )
    (net (code "54") (name "Net-(U2-INH)") (class "Default")
      (node (ref "R14") (pin "2") (pinfunction "2_2") (pintype "passive"))
      (node (ref "U2") (pin "3") (pinfunction "INH_3") (pintype "input"))
    )
    (net (code "55") (name "Net-(U2-IS)") (class "Default")
      (node (ref "R16") (pin "2") (pinfunction "2_2") (pintype "passive"))
      (node (ref "U2") (pin "6") (pinfunction "IS_6") (pintype "output"))
    )
    (net (code "56") (name "Net-(U2-SR)") (class "Default")
      (node (ref "R15") (pin "2") (pinfunction "2_2") (pintype "passive"))
      (node (ref "U2") (pin "5") (pinfunction "SR_5") (pintype "input"))
    )
    (net (code "57") (name "Net-(U3-FB)") (class "Default")
      (node (ref "R21") (pin "1") (pinfunction "1_1") (pintype "passive"))
      (node (ref "R8") (pin "1") (pinfunction "1_1") (pintype "passive"))
      (node (ref "U3") (pin "2") (pinfunction "FB_2") (pintype "input"))
    )
    (net (code "58") (name "Net-(U3-VC)") (class "Default")
      (node (ref "C3") (pin "2") (pinfunction "2_2") (pintype "passive"))
      (node (ref "U3") (pin "4") (pinfunction "VC_4") (pintype "passive"))
    )
    (net (code "59") (name "Net-(VR1-OUTPUT)") (class "Default")
      (node (ref "D1") (pin "C") (pinfunction "C_C") (pintype "passive"))
      (node (ref "L1") (pin "1") (pinfunction "1_1") (pintype "passive"))
      (node (ref "VR1") (pin "2") (pinfunction "OUTPUT_2") (pintype "output"))
    )
    (net (code "60") (name "Net-(VR1-~{ON}{slash}OFF)") (class "Default")
      (node (ref "R3") (pin "1") (pinfunction "1_1") (pintype "passive"))
      (node (ref "R4") (pin "2") (pinfunction "2_2") (pintype "passive"))
      (node (ref "U$3") (pin "C") (pinfunction "C_C") (pintype "passive"))
      (node (ref "VR1") (pin "5") (pinfunction "~{ON}/OFF_5") (pintype "input"))
      (node (ref "VR2") (pin "5") (pinfunction "~{ON}/OFF_5") (pintype "input"))
      (node (ref "VR5") (pin "5") (pinfunction "~{ON}/OFF_5") (pintype "input"))
    )
    (net (code "61") (name "Net-(VR2-FEEDBACK)") (class "Default")
      (node (ref "R5") (pin "1") (pinfunction "1_1") (pintype "passive"))
      (node (ref "R6") (pin "1") (pinfunction "1_1") (pintype "passive"))
      (node (ref "VR2") (pin "4") (pinfunction "FEEDBACK_4") (pintype "input"))
    )
    (net (code "62") (name "Net-(VR2-OUTPUT)") (class "Default")
      (node (ref "D3") (pin "C") (pinfunction "C_C") (pintype "passive"))
      (node (ref "L2") (pin "1") (pinfunction "1_1") (pintype "passive"))
      (node (ref "VR2") (pin "2") (pinfunction "OUTPUT_2") (pintype "output"))
    )
    (net (code "63") (name "Net-(VR5-FEEDBACK)") (class "Default")
      (node (ref "R29") (pin "1") (pinfunction "1_1") (pintype "passive"))
      (node (ref "R30") (pin "1") (pinfunction "1_1") (pintype "passive"))
      (node (ref "VR5") (pin "4") (pinfunction "FEEDBACK_4") (pintype "input"))
    )
    (net (code "64") (name "Net-(VR5-OUTPUT)") (class "Default")
      (node (ref "D9") (pin "C") (pinfunction "C_C") (pintype "passive"))
      (node (ref "L5") (pin "1") (pinfunction "1_1") (pintype "passive"))
      (node (ref "VR5") (pin "2") (pinfunction "OUTPUT_2") (pintype "output"))
    )
    (net (code "65") (name "Net-(X2A-S)") (class "Default")
      (node (ref "U1") (pin "4") (pinfunction "OUT_4") (pintype "output"))
      (node (ref "U1") (pin "8") (pinfunction "OUT_8") (pintype "output"))
      (node (ref "X2") (pin "1") (pinfunction "S_1") (pintype "passive"))
    )
    (net (code "66") (name "Net-(X3A-S)") (class "Default")
      (node (ref "U2") (pin "4") (pinfunction "OUT_4") (pintype "output"))
      (node (ref "U2") (pin "8") (pinfunction "OUT_8") (pintype "output"))
      (node (ref "X3") (pin "1") (pinfunction "S_1") (pintype "passive"))
    )
    (net (code "67") (name "Net-(X6A-S)") (class "Default")
      (node (ref "K1") (pin "S") (pinfunction "S_S") (pintype "passive"))
      (node (ref "X6") (pin "1") (pinfunction "S_1") (pintype "passive"))
    )
    (net (code "68") (name "Net-(X8A-S)") (class "Default")
      (node (ref "K3") (pin "S") (pinfunction "S_S") (pintype "passive"))
      (node (ref "X8") (pin "1") (pinfunction "S_1") (pintype "passive"))
    )
    (net (code "69") (name "Net-(X10A-S)") (class "Default")
      (node (ref "K4") (pin "P") (pinfunction "P_P") (pintype "passive"))
      (node (ref "X10") (pin "1") (pinfunction "S_1") (pintype "passive"))
    )
    (net (code "70") (name "Net-(X10B-S)") (class "Default")
      (node (ref "K4") (pin "S") (pinfunction "S_S") (pintype "passive"))
      (node (ref "X10") (pin "2") (pinfunction "S_2") (pintype "passive"))
    )
    (net (code "71") (name "unconnected-(K1-PadO)") (class "Default")
      (node (ref "K1") (pin "O") (pinfunction "O_O") (pintype "passive"))
    )
    (net (code "72") (name "unconnected-(K3-PadO)") (class "Default")
      (node (ref "K3") (pin "O") (pinfunction "O_O") (pintype "passive"))
    )
    (net (code "73") (name "unconnected-(K4-PadO)") (class "Default")
      (node (ref "K4") (pin "O") (pinfunction "O_O") (pintype "passive"))
    )
    (net (code "74") (name "unconnected-(U$9-3V3-Pad1)") (class "Default")
      (node (ref "U$9") (pin "1") (pinfunction "3V3_1") (pintype "bidirectional"))
    )
    (net (code "75") (name "unconnected-(U$9-CLK-Pad20)") (class "Default")
      (node (ref "U$9") (pin "20") (pinfunction "CLK_20") (pintype "bidirectional"))
    )
    (net (code "76") (name "unconnected-(U$9-CMD-Pad18)") (class "Default")
      (node (ref "U$9") (pin "18") (pinfunction "CMD_18") (pintype "bidirectional"))
    )
    (net (code "77") (name "unconnected-(U$9-GND-Pad14)") (class "Default")
      (node (ref "U$9") (pin "14") (pinfunction "GND_14") (pintype "bidirectional"))
    )
    (net (code "78") (name "unconnected-(U$9-GND-Pad32)") (class "Default")
      (node (ref "U$9") (pin "32") (pinfunction "GND_32") (pintype "bidirectional"))
    )
    (net (code "79") (name "unconnected-(U$9-IO0-Pad25)") (class "Default")
      (node (ref "U$9") (pin "25") (pinfunction "IO0_25") (pintype "bidirectional"))
    )
    (net (code "80") (name "unconnected-(U$9-IO5-Pad29)") (class "Default")
      (node (ref "U$9") (pin "29") (pinfunction "IO5_29") (pintype "bidirectional"))
    )
    (net (code "81") (name "unconnected-(U$9-IO12-Pad13)") (class "Default")
      (node (ref "U$9") (pin "13") (pinfunction "IO12_13") (pintype "bidirectional"))
    )
    (net (code "82") (name "unconnected-(U$9-RXD0-Pad34)") (class "Default")
      (node (ref "U$9") (pin "34") (pinfunction "RXD0_34") (pintype "bidirectional"))
    )
    (net (code "83") (name "unconnected-(U$9-SD0-Pad21)") (class "Default")
      (node (ref "U$9") (pin "21") (pinfunction "SD0_21") (pintype "bidirectional"))
    )
    (net (code "84") (name "unconnected-(U$9-SD1-Pad22)") (class "Default")
      (node (ref "U$9") (pin "22") (pinfunction "SD1_22") (pintype "bidirectional"))
    )
    (net (code "85") (name "unconnected-(U$9-SD2-Pad16)") (class "Default")
      (node (ref "U$9") (pin "16") (pinfunction "SD2_16") (pintype "bidirectional"))
    )
    (net (code "86") (name "unconnected-(U$9-SD3-Pad17)") (class "Default")
      (node (ref "U$9") (pin "17") (pinfunction "SD3_17") (pintype "bidirectional"))
    )
    (net (code "87") (name "unconnected-(U$9-TXD0-Pad35)") (class "Default")
      (node (ref "U$9") (pin "35") (pinfunction "TXD0_35") (pintype "bidirectional"))
    )
  )
)
